# schema.net
KiCad netlist of a schematic drawn in EAGLE
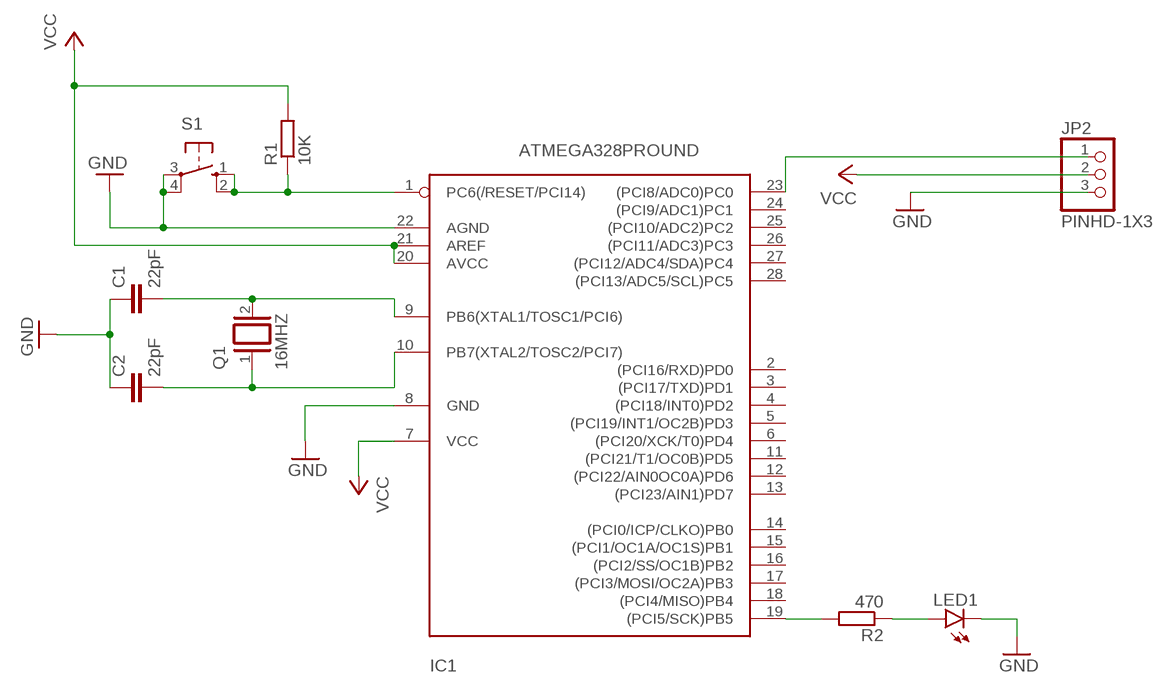
[diagram p0: schematic, sheet 1]

(export (version "E")
  (design (tool "Eeschema 10.0.6"))
  (components
    (comp (ref "C1")
      (value "22pF")
      (footprint "eagle-import:C025-025X050")
      (libsource (lib "eagle-import") (part "C-EU025-025X050"))
    )
    (comp (ref "C2")
      (value "22pF")
      (footprint "eagle-import:C025-025X050")
      (libsource (lib "eagle-import") (part "C-EU025-025X050"))
    )
    (comp (ref "IC1")
      (value "ATMEGA328PROUND")
      (footprint "eagle-import:DIL28-3-ROUND")
      (libsource (lib "eagle-import") (part "ATMEGA328PROUND"))
    )
    (comp (ref "JP2")
      (value "PINHD-1X3")
      (footprint "eagle-import:1X03")
      (libsource (lib "eagle-import") (part "PINHD-1X3"))
    )
    (comp (ref "LED1")
      (value "LED3MM")
      (footprint "eagle-import:LED3MM")
      (libsource (lib "eagle-import") (part "LED3MM"))
    )
    (comp (ref "Q1")
      (value "16MHZ")
      (footprint "eagle-import:QS")
      (libsource (lib "eagle-import") (part "XTAL/S"))
    )
    (comp (ref "R1")
      (value "10K")
      (footprint "eagle-import:0204_7")
      (libsource (lib "eagle-import") (part "R-EU_0204/7"))
    )
    (comp (ref "R2")
      (value "470")
      (footprint "eagle-import:0204_7")
      (libsource (lib "eagle-import") (part "R-EU_0204/7"))
    )
    (comp (ref "S1")
      (value "10-XX")
      (footprint "eagle-import:B3F-10XX")
      (fields (field (name "MPN") "B3F-1000"))
      (libsource (lib "eagle-import") (part "10-XX"))
    )
  )
  (nets
    (net (code "1") (name "GND") (class "Default")
      (node (ref "C1") (pin "1") (pinfunction "1_1") (pintype "passive"))
      (node (ref "C2") (pin "1") (pinfunction "1_1") (pintype "passive"))
      (node (ref "IC1") (pin "22") (pinfunction "AGND_22") (pintype "bidirectional"))
      (node (ref "IC1") (pin "8") (pinfunction "GND_8") (pintype "bidirectional"))
      (node (ref "JP2") (pin "3") (pinfunction "3_3") (pintype "passive"))
      (node (ref "LED1") (pin "K") (pinfunction "C_K") (pintype "passive"))
      (node (ref "S1") (pin "3") (pinfunction "P_3") (pintype "passive"))
      (node (ref "S1") (pin "4") (pinfunction "P1_4") (pintype "passive"))
    )
    (net (code "2") (name "Net-(IC1-(PCI5{slash}SCK)PB5)") (class "Default")
      (node (ref "IC1") (pin "19") (pinfunction "(PCI5/SCK)PB5_19") (pintype "bidirectional"))
      (node (ref "R2") (pin "2") (pinfunction "2_2") (pintype "passive"))
    )
    (net (code "3") (name "Net-(IC1-(PCI8{slash}ADC0)PC0)") (class "Default")
      (node (ref "IC1") (pin "23") (pinfunction "(PCI8/ADC0)PC0_23") (pintype "bidirectional"))
      (node (ref "JP2") (pin "1") (pinfunction "1_1") (pintype "passive"))
    )
    (net (code "4") (name "Net-(IC1-PB6(XTAL1{slash}TOSC1{slash}PCI6))") (class "Default")
      (node (ref "C1") (pin "2") (pinfunction "2_2") (pintype "passive"))
      (node (ref "IC1") (pin "9") (pinfunction "PB6(XTAL1/TOSC1/PCI6)_9") (pintype "bidirectional"))
      (node (ref "Q1") (pin "2") (pinfunction "2_2") (pintype "passive"))
    )
    (net (code "5") (name "Net-(IC1-PB7(XTAL2{slash}TOSC2{slash}PCI7))") (class "Default")
      (node (ref "C2") (pin "2") (pinfunction "2_2") (pintype "passive"))
      (node (ref "IC1") (pin "10") (pinfunction "PB7(XTAL2/TOSC2/PCI7)_10") (pintype "bidirectional"))
      (node (ref "Q1") (pin "1") (pinfunction "1_1") (pintype "passive"))
    )
    (net (code "6") (name "Net-(IC1-PC6({slash}RESET{slash}PCI14))") (class "Default")
      (node (ref "IC1") (pin "1") (pinfunction "PC6(/RESET/PCI14)_1") (pintype "bidirectional"))
      (node (ref "R1") (pin "1") (pinfunction "1_1") (pintype "passive"))
      (node (ref "S1") (pin "1") (pinfunction "S_1") (pintype "passive"))
      (node (ref "S1") (pin "2") (pinfunction "S1_2") (pintype "passive"))
    )
    (net (code "7") (name "Net-(LED1-PadA)") (class "Default")
      (node (ref "LED1") (pin "A") (pinfunction "A_A") (pintype "passive"))
      (node (ref "R2") (pin "1") (pinfunction "1_1") (pintype "passive"))
    )
    (net (code "8") (name "VCC") (class "Default")
      (node (ref "IC1") (pin "20") (pinfunction "AVCC_20") (pintype "bidirectional"))
      (node (ref "IC1") (pin "21") (pinfunction "AREF_21") (pintype "bidirectional"))
      (node (ref "IC1") (pin "7") (pinfunction "VCC_7") (pintype "bidirectional"))
      (node (ref "JP2") (pin "2") (pinfunction "2_2") (pintype "passive"))
      (node (ref "R1") (pin "2") (pinfunction "2_2") (pintype "passive"))
    )
    (net (code "9") (name "unconnected-(IC1-(PCI0{slash}ICP{slash}CLKO)PB0-Pad14)") (class "Default")
      (node (ref "IC1") (pin "14") (pinfunction "(PCI0/ICP/CLKO)PB0_14") (pintype "bidirectional"))
    )
    (net (code "10") (name "unconnected-(IC1-(PCI1{slash}OC1A{slash}OC1S)PB1-Pad15)") (class "Default")
      (node (ref "IC1") (pin "15") (pinfunction "(PCI1/OC1A/OC1S)PB1_15") (pintype "bidirectional"))
    )
    (net (code "11") (name "unconnected-(IC1-(PCI2{slash}SS{slash}OC1B)PB2-Pad16)") (class "Default")
      (node (ref "IC1") (pin "16") (pinfunction "(PCI2/SS/OC1B)PB2_16") (pintype "bidirectional"))
    )
    (net (code "12") (name "unconnected-(IC1-(PCI3{slash}MOSI{slash}OC2A)PB3-Pad17)") (class "Default")
      (node (ref "IC1") (pin "17") (pinfunction "(PCI3/MOSI/OC2A)PB3_17") (pintype "bidirectional"))
    )
    (net (code "13") (name "unconnected-(IC1-(PCI4{slash}MISO)PB4-Pad18)") (class "Default")
      (node (ref "IC1") (pin "18") (pinfunction "(PCI4/MISO)PB4_18") (pintype "bidirectional"))
    )
    (net (code "14") (name "unconnected-(IC1-(PCI9{slash}ADC1)PC1-Pad24)") (class "Default")
      (node (ref "IC1") (pin "24") (pinfunction "(PCI9/ADC1)PC1_24") (pintype "bidirectional"))
    )
    (net (code "15") (name "unconnected-(IC1-(PCI10{slash}ADC2)PC2-Pad25)") (class "Default")
      (node (ref "IC1") (pin "25") (pinfunction "(PCI10/ADC2)PC2_25") (pintype "bidirectional"))
    )
    (net (code "16") (name "unconnected-(IC1-(PCI11{slash}ADC3)PC3-Pad26)") (class "Default")
      (node (ref "IC1") (pin "26") (pinfunction "(PCI11/ADC3)PC3_26") (pintype "bidirectional"))
    )
    (net (code "17") (name "unconnected-(IC1-(PCI12{slash}ADC4{slash}SDA)PC4-Pad27)") (class "Default")
      (node (ref "IC1") (pin "27") (pinfunction "(PCI12/ADC4/SDA)PC4_27") (pintype "bidirectional"))
    )
    (net (code "18") (name "unconnected-(IC1-(PCI13{slash}ADC5{slash}SCL)PC5-Pad28)") (class "Default")
      (node (ref "IC1") (pin "28") (pinfunction "(PCI13/ADC5/SCL)PC5_28") (pintype "bidirectional"))
    )
    (net (code "19") (name "unconnected-(IC1-(PCI16{slash}RXD)PD0-Pad2)") (class "Default")
      (node (ref "IC1") (pin "2") (pinfunction "(PCI16/RXD)PD0_2") (pintype "bidirectional"))
    )
    (net (code "20") (name "unconnected-(IC1-(PCI17{slash}TXD)PD1-Pad3)") (class "Default")
      (node (ref "IC1") (pin "3") (pinfunction "(PCI17/TXD)PD1_3") (pintype "bidirectional"))
    )
    (net (code "21") (name "unconnected-(IC1-(PCI18{slash}INT0)PD2-Pad4)") (class "Default")
      (node (ref "IC1") (pin "4") (pinfunction "(PCI18/INT0)PD2_4") (pintype "bidirectional"))
    )
    (net (code "22") (name "unconnected-(IC1-(PCI19{slash}INT1{slash}OC2B)PD3-Pad5)") (class "Default")
      (node (ref "IC1") (pin "5") (pinfunction "(PCI19/INT1/OC2B)PD3_5") (pintype "bidirectional"))
    )
    (net (code "23") (name "unconnected-(IC1-(PCI20{slash}XCK{slash}T0)PD4-Pad6)") (class "Default")
      (node (ref "IC1") (pin "6") (pinfunction "(PCI20/XCK/T0)PD4_6") (pintype "bidirectional"))
    )
    (net (code "24") (name "unconnected-(IC1-(PCI21{slash}T1{slash}OC0B)PD5-Pad11)") (class "Default")
      (node (ref "IC1") (pin "11") (pinfunction "(PCI21/T1/OC0B)PD5_11") (pintype "bidirectional"))
    )
    (net (code "25") (name "unconnected-(IC1-(PCI22{slash}AIN0OC0A)PD6-Pad12)") (class "Default")
      (node (ref "IC1") (pin "12") (pinfunction "(PCI22/AIN0OC0A)PD6_12") (pintype "bidirectional"))
    )
    (net (code "26") (name "unconnected-(IC1-(PCI23{slash}AIN1)PD7-Pad13)") (class "Default")
      (node (ref "IC1") (pin "13") (pinfunction "(PCI23/AIN1)PD7_13") (pintype "bidirectional"))
    )
  )
)
